# IsolatedPortOut.net
KiCad netlist of a schematic drawn in Altium Designer
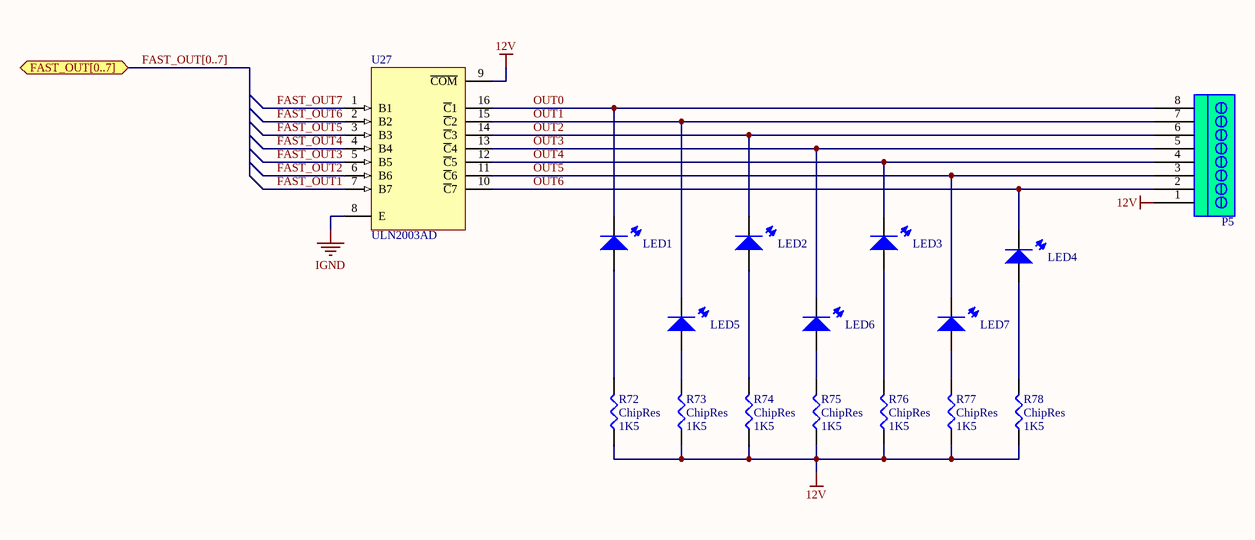
[diagram p0: IsolatedPortOut.SchDoc]

(export (version "E")
  (design (tool "Eeschema 10.0.6"))
  (components
    (comp (ref "LED1") (value "LED 0603") (footprint "LED 0603") (libsource (lib "LEDs") (part "LED0603")))
    (comp (ref "LED2") (value "LED 0603") (footprint "LED 0603") (libsource (lib "LEDs") (part "LED0603")))
    (comp (ref "LED3") (value "LED 0603") (footprint "LED 0603") (libsource (lib "LEDs") (part "LED0603")))
    (comp (ref "LED4") (value "LED 0603") (footprint "LED 0603") (libsource (lib "LEDs") (part "LED0603")))
    (comp (ref "LED5") (value "LED 0603") (footprint "LED 0603") (libsource (lib "LEDs") (part "LED0603")))
    (comp (ref "LED6") (value "LED 0603") (footprint "LED 0603") (libsource (lib "LEDs") (part "LED0603")))
    (comp (ref "LED7") (value "LED 0603") (footprint "LED 0603") (libsource (lib "LEDs") (part "LED0603")))
    (comp (ref "P5")
      (value "Terminal Block 8x5.08mm")
      (footprint "SOCKET 8x5.08")
      (description "Terminal Block Socket Right Angle 8x5.08mm 2-Wall")
      (libsource (lib "IndustrialConnectors") (part "Socket_8x5.08_RA_2Wall"))
    )
    (comp (ref "R72")
      (value "ChipRes")
      (footprint "RES0805")
      (description "Chip resistor")
      (fields (field (name "ALTIUM_VALUE") "1K5"))
      (libsource (lib "Common Devices") (part "ChipRes"))
    )
    (comp (ref "R73")
      (value "ChipRes")
      (footprint "RES0805")
      (description "Chip resistor")
      (fields (field (name "ALTIUM_VALUE") "1K5"))
      (libsource (lib "Common Devices") (part "ChipRes"))
    )
    (comp (ref "R74")
      (value "ChipRes")
      (footprint "RES0805")
      (description "Chip resistor")
      (fields (field (name "ALTIUM_VALUE") "1K5"))
      (libsource (lib "Common Devices") (part "ChipRes"))
    )
    (comp (ref "R75")
      (value "ChipRes")
      (footprint "RES0805")
      (description "Chip resistor")
      (fields (field (name "ALTIUM_VALUE") "1K5"))
      (libsource (lib "Common Devices") (part "ChipRes"))
    )
    (comp (ref "R76")
      (value "ChipRes")
      (footprint "RES0805")
      (description "Chip resistor")
      (fields (field (name "ALTIUM_VALUE") "1K5"))
      (libsource (lib "Common Devices") (part "ChipRes"))
    )
    (comp (ref "R77")
      (value "ChipRes")
      (footprint "RES0805")
      (description "Chip resistor")
      (fields (field (name "ALTIUM_VALUE") "1K5"))
      (libsource (lib "Common Devices") (part "ChipRes"))
    )
    (comp (ref "R78")
      (value "ChipRes")
      (footprint "RES0805")
      (description "Chip resistor")
      (fields (field (name "ALTIUM_VALUE") "1K5"))
      (libsource (lib "Common Devices") (part "ChipRes"))
    )
    (comp (ref "U27")
      (value "ULN2003AD")
      (footprint "D016_N")
      (description "Darlington Transistor Array")
      (fields (field (name "PUBLISHER") "Altium Limited"))
      (libsource (lib "TI Interface Darlington Driver") (part "ULN2003AD"))
    )
  )
  (nets
    (net (code "2") (name "/FAST_OUT1") (class "Default")
      (node (ref "U27") (pin "7") (pinfunction "B7_7") (pintype "input"))
    )
    (net (code "3") (name "/FAST_OUT2") (class "Default")
      (node (ref "U27") (pin "6") (pinfunction "B6_6") (pintype "input"))
    )
    (net (code "4") (name "/FAST_OUT3") (class "Default")
      (node (ref "U27") (pin "5") (pinfunction "B5_5") (pintype "input"))
    )
    (net (code "5") (name "/FAST_OUT4") (class "Default")
      (node (ref "U27") (pin "4") (pinfunction "B4_4") (pintype "input"))
    )
    (net (code "6") (name "/FAST_OUT5") (class "Default")
      (node (ref "U27") (pin "3") (pinfunction "B3_3") (pintype "input"))
    )
    (net (code "7") (name "/FAST_OUT6") (class "Default")
      (node (ref "U27") (pin "2") (pinfunction "B2_2") (pintype "input"))
    )
    (net (code "8") (name "/FAST_OUT7") (class "Default")
      (node (ref "U27") (pin "1") (pinfunction "B1_1") (pintype "input"))
    )
    (net (code "10") (name "/OUT0") (class "Default")
      (node (ref "LED1") (pin "1") (pinfunction "1_1") (pintype "passive"))
      (node (ref "P5") (pin "8") (pintype "passive"))
      (node (ref "U27") (pin "16") (pinfunction "~{C}1_16") (pintype "open_collector"))
    )
    (net (code "11") (name "/OUT1") (class "Default")
      (node (ref "LED5") (pin "1") (pinfunction "1_1") (pintype "passive"))
      (node (ref "P5") (pin "7") (pintype "passive"))
      (node (ref "U27") (pin "15") (pinfunction "~{C}2_15") (pintype "open_collector"))
    )
    (net (code "12") (name "/OUT2") (class "Default")
      (node (ref "LED2") (pin "1") (pinfunction "1_1") (pintype "passive"))
      (node (ref "P5") (pin "6") (pintype "passive"))
      (node (ref "U27") (pin "14") (pinfunction "~{C}3_14") (pintype "open_collector"))
    )
    (net (code "13") (name "/OUT3") (class "Default")
      (node (ref "LED6") (pin "1") (pinfunction "1_1") (pintype "passive"))
      (node (ref "P5") (pin "5") (pintype "passive"))
      (node (ref "U27") (pin "13") (pinfunction "~{C}4_13") (pintype "open_collector"))
    )
    (net (code "14") (name "/OUT4") (class "Default")
      (node (ref "LED3") (pin "1") (pinfunction "1_1") (pintype "passive"))
      (node (ref "P5") (pin "4") (pintype "passive"))
      (node (ref "U27") (pin "12") (pinfunction "~{C}5_12") (pintype "open_collector"))
    )
    (net (code "15") (name "/OUT5") (class "Default")
      (node (ref "LED7") (pin "1") (pinfunction "1_1") (pintype "passive"))
      (node (ref "P5") (pin "3") (pintype "passive"))
      (node (ref "U27") (pin "11") (pinfunction "~{C}6_11") (pintype "open_collector"))
    )
    (net (code "16") (name "/OUT6") (class "Default")
      (node (ref "LED4") (pin "1") (pinfunction "1_1") (pintype "passive"))
      (node (ref "P5") (pin "2") (pintype "passive"))
      (node (ref "U27") (pin "10") (pinfunction "~{C}7_10") (pintype "open_collector"))
    )
    (net (code "17") (name "12V") (class "Default")
      (node (ref "P5") (pin "1") (pintype "passive"))
      (node (ref "R72") (pin "1") (pintype "passive"))
      (node (ref "R73") (pin "1") (pintype "passive"))
      (node (ref "R74") (pin "1") (pintype "passive"))
      (node (ref "R75") (pin "1") (pintype "passive"))
      (node (ref "R76") (pin "1") (pintype "passive"))
      (node (ref "R77") (pin "1") (pintype "passive"))
      (node (ref "R78") (pin "1") (pintype "passive"))
      (node (ref "U27") (pin "9") (pinfunction "~{COM}_9") (pintype "passive"))
    )
    (net (code "18") (name "IGND") (class "Default")
      (node (ref "U27") (pin "8") (pinfunction "E_8") (pintype "power_in"))
    )
    (net (code "19") (name "Net-(LED1-Pad2)") (class "Default")
      (node (ref "LED1") (pin "2") (pinfunction "2_2") (pintype "passive"))
      (node (ref "R72") (pin "2") (pintype "passive"))
    )
    (net (code "20") (name "Net-(LED2-Pad2)") (class "Default")
      (node (ref "LED2") (pin "2") (pinfunction "2_2") (pintype "passive"))
      (node (ref "R74") (pin "2") (pintype "passive"))
    )
    (net (code "21") (name "Net-(LED3-Pad2)") (class "Default")
      (node (ref "LED3") (pin "2") (pinfunction "2_2") (pintype "passive"))
      (node (ref "R76") (pin "2") (pintype "passive"))
    )
    (net (code "22") (name "Net-(LED4-Pad2)") (class "Default")
      (node (ref "LED4") (pin "2") (pinfunction "2_2") (pintype "passive"))
      (node (ref "R78") (pin "2") (pintype "passive"))
    )
    (net (code "23") (name "Net-(LED5-Pad2)") (class "Default")
      (node (ref "LED5") (pin "2") (pinfunction "2_2") (pintype "passive"))
      (node (ref "R73") (pin "2") (pintype "passive"))
    )
    (net (code "24") (name "Net-(LED6-Pad2)") (class "Default")
      (node (ref "LED6") (pin "2") (pinfunction "2_2") (pintype "passive"))
      (node (ref "R75") (pin "2") (pintype "passive"))
    )
    (net (code "25") (name "Net-(LED7-Pad2)") (class "Default")
      (node (ref "LED7") (pin "2") (pinfunction "2_2") (pintype "passive"))
      (node (ref "R77") (pin "2") (pintype "passive"))
    )
  )
)
